# wireless.net
KiCad netlist of a schematic drawn in Altium Designer
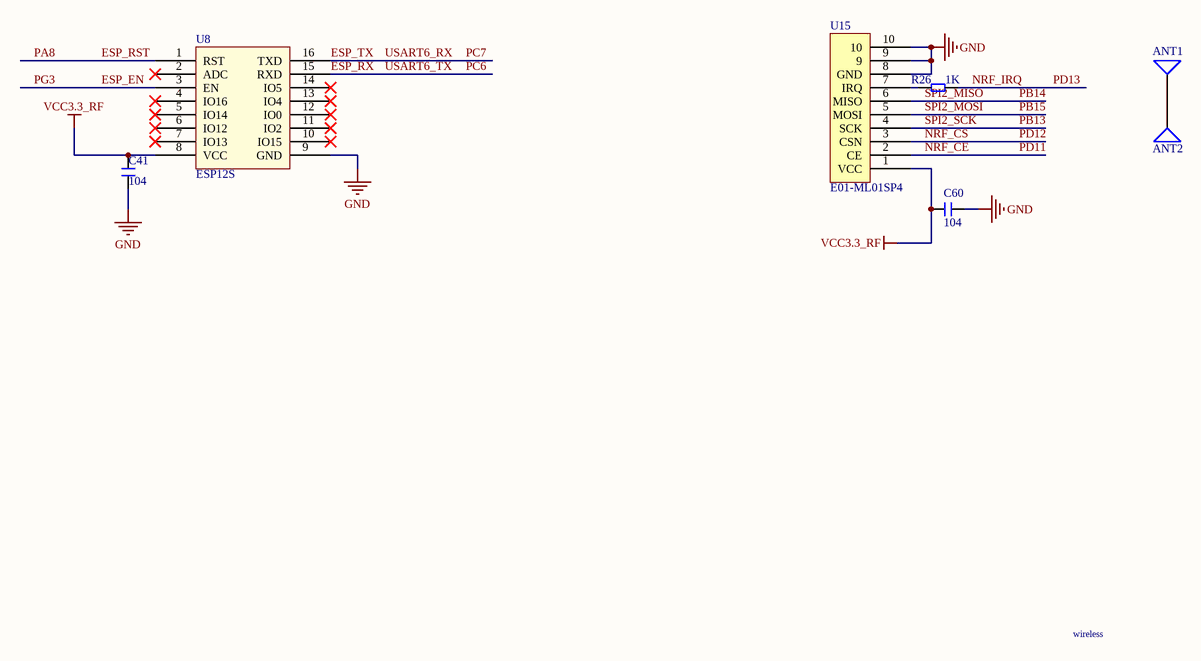
[diagram p0: wireless.SchDoc]

(export (version "E")
  (design (tool "Eeschema 10.0.6"))
  (components
    (comp (ref "ANT1") (value "ANT1") (footprint "ANT-SMA-KE") (libsource (lib "squ-guiboard") (part "ANT")))
    (comp (ref "ANT2") (value "ANT") (footprint "ANT IPEX") (libsource (lib "squ-guiboard") (part "ANT")))
    (comp (ref "C41") (value "104") (footprint "C 0603") (libsource (lib "Bison-Board") (part "CAP")))
    (comp (ref "C60") (value "104") (footprint "C 0603") (libsource (lib "Bison-Board") (part "CAP")))
    (comp (ref "R26") (value "1K") (footprint "R 0603") (libsource (lib "Bison-Board") (part "RES")))
    (comp (ref "U8")
      (value "ESP12S")
      (footprint "ESP12S")
      (description "WIFI模块")
      (libsource (lib "Bison-Board") (part "ESP12S"))
    )
    (comp (ref "U15")
      (value "E01-ML01SP4")
      (footprint "E01-ML01SP4")
      (description "2.4G无限模块")
      (libsource (lib "Bison-Board") (part "24L01"))
    )
  )
  (nets
    (net (code "1") (name "/ESP_EN") (class "Default")
      (node (ref "U8") (pin "3") (pinfunction "EN_3") (pintype "passive"))
    )
    (net (code "2") (name "/ESP_RST") (class "Default")
      (node (ref "U8") (pin "1") (pinfunction "RST_1") (pintype "passive"))
    )
    (net (code "3") (name "/ESP_RX") (class "Default")
      (node (ref "U8") (pin "15") (pinfunction "RXD_15") (pintype "passive"))
    )
    (net (code "4") (name "/ESP_TX") (class "Default")
      (node (ref "U8") (pin "16") (pinfunction "TXD_16") (pintype "passive"))
    )
    (net (code "5") (name "/NRF_CE") (class "Default")
      (node (ref "U15") (pin "2") (pinfunction "CE_2") (pintype "passive"))
    )
    (net (code "6") (name "/NRF_CS") (class "Default")
      (node (ref "U15") (pin "3") (pinfunction "CSN_3") (pintype "passive"))
    )
    (net (code "7") (name "/NRF_IRQ") (class "Default") (node (ref "R26") (pin "1") (pintype "passive")))
    (net (code "8") (name "/PB13") (class "Default")
      (node (ref "U15") (pin "4") (pinfunction "SCK_4") (pintype "passive"))
    )
    (net (code "9") (name "/PB14") (class "Default")
      (node (ref "U15") (pin "6") (pinfunction "MISO_6") (pintype "passive"))
    )
    (net (code "10") (name "/PB15") (class "Default")
      (node (ref "U15") (pin "5") (pinfunction "MOSI_5") (pintype "passive"))
    )
    (net (code "11") (name "GND") (class "Default")
      (node (ref "C41") (pin "1") (pinfunction "1_1") (pintype "passive"))
      (node (ref "C60") (pin "2") (pinfunction "2_2") (pintype "passive"))
      (node (ref "U15") (pin "10") (pinfunction "10_10") (pintype "passive"))
      (node (ref "U15") (pin "8") (pinfunction "GND_8") (pintype "passive"))
      (node (ref "U15") (pin "9") (pinfunction "9_9") (pintype "passive"))
      (node (ref "U8") (pin "9") (pinfunction "GND_9") (pintype "passive"))
    )
    (net (code "12") (name "Net-(ANT1-Pad1)") (class "Default")
      (node (ref "ANT1") (pin "1") (pinfunction "1_1") (pintype "passive"))
      (node (ref "ANT2") (pin "1") (pinfunction "1_1") (pintype "passive"))
    )
    (net (code "13") (name "Net-(U15-IRQ)") (class "Default")
      (node (ref "R26") (pin "2") (pintype "passive"))
      (node (ref "U15") (pin "7") (pinfunction "IRQ_7") (pintype "passive"))
    )
    (net (code "14") (name "VCC3.3_RF") (class "Default")
      (node (ref "C41") (pin "2") (pinfunction "2_2") (pintype "passive"))
      (node (ref "C60") (pin "1") (pinfunction "1_1") (pintype "passive"))
      (node (ref "U15") (pin "1") (pinfunction "VCC_1") (pintype "passive"))
      (node (ref "U8") (pin "8") (pinfunction "VCC_8") (pintype "passive"))
    )
    (net (code "15") (name "unconnected-(U8-ADC-Pad2)") (class "Default")
      (node (ref "U8") (pin "2") (pinfunction "ADC_2") (pintype "passive+no_connect"))
    )
    (net (code "16") (name "unconnected-(U8-IO0-Pad12)") (class "Default")
      (node (ref "U8") (pin "12") (pinfunction "IO0_12") (pintype "passive+no_connect"))
    )
    (net (code "17") (name "unconnected-(U8-IO2-Pad11)") (class "Default")
      (node (ref "U8") (pin "11") (pinfunction "IO2_11") (pintype "passive+no_connect"))
    )
    (net (code "18") (name "unconnected-(U8-IO4-Pad13)") (class "Default")
      (node (ref "U8") (pin "13") (pinfunction "IO4_13") (pintype "passive+no_connect"))
    )
    (net (code "19") (name "unconnected-(U8-IO5-Pad14)") (class "Default")
      (node (ref "U8") (pin "14") (pinfunction "IO5_14") (pintype "passive+no_connect"))
    )
    (net (code "20") (name "unconnected-(U8-IO12-Pad6)") (class "Default")
      (node (ref "U8") (pin "6") (pinfunction "IO12_6") (pintype "passive+no_connect"))
    )
    (net (code "21") (name "unconnected-(U8-IO13-Pad7)") (class "Default")
      (node (ref "U8") (pin "7") (pinfunction "IO13_7") (pintype "passive+no_connect"))
    )
    (net (code "22") (name "unconnected-(U8-IO14-Pad5)") (class "Default")
      (node (ref "U8") (pin "5") (pinfunction "IO14_5") (pintype "passive+no_connect"))
    )
    (net (code "23") (name "unconnected-(U8-IO15-Pad10)") (class "Default")
      (node (ref "U8") (pin "10") (pinfunction "IO15_10") (pintype "passive+no_connect"))
    )
    (net (code "24") (name "unconnected-(U8-IO16-Pad4)") (class "Default")
      (node (ref "U8") (pin "4") (pinfunction "IO16_4") (pintype "passive+no_connect"))
    )
  )
)
